# HIVDC.net
KiCad netlist of a schematic drawn in EAGLE
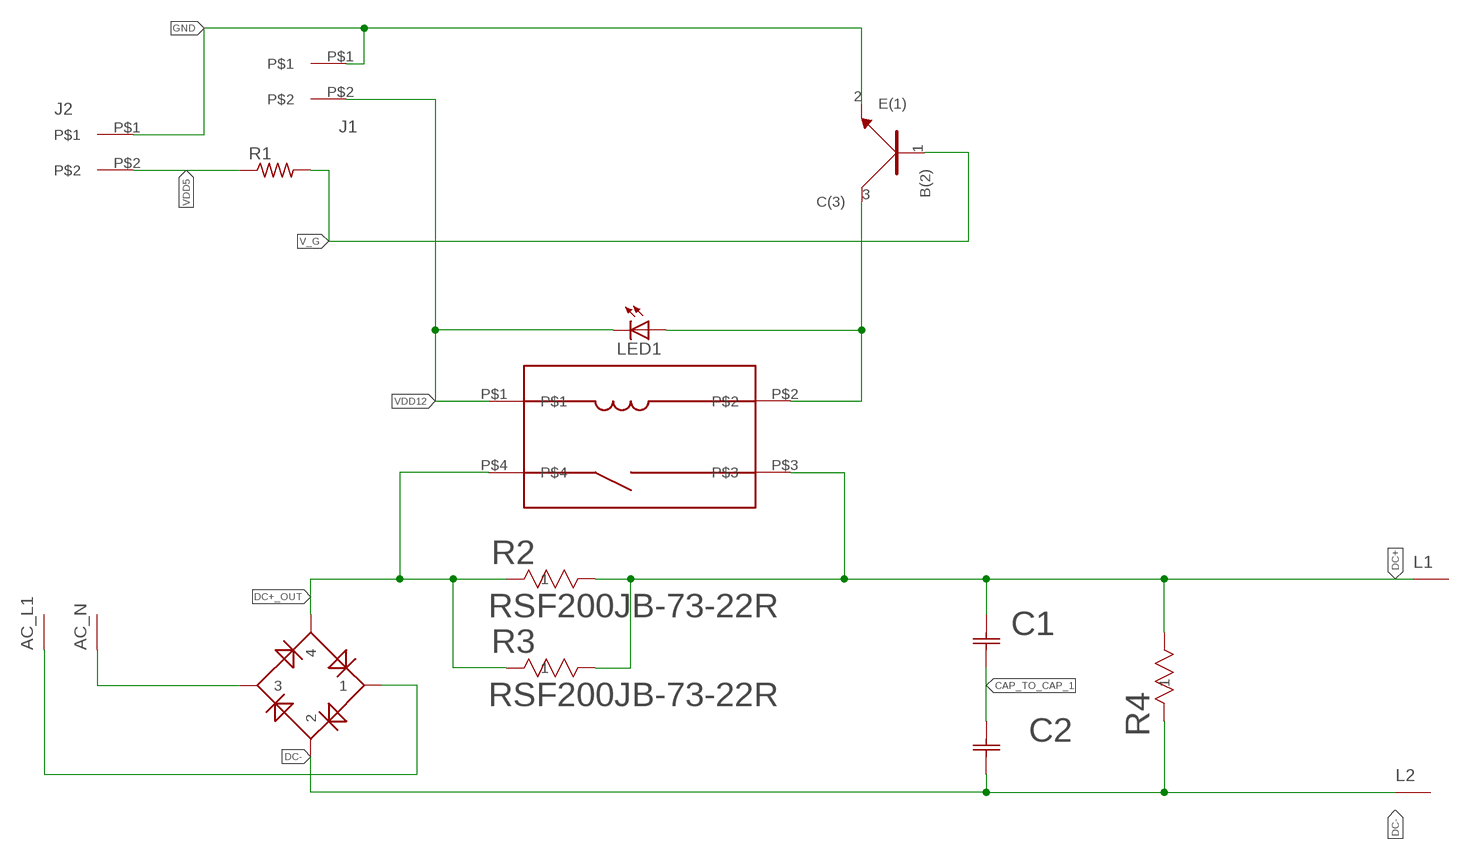
[diagram p0: schematic, sheet 1]

(export (version "E")
  (design (tool "Eeschema 10.0.6"))
  (components
    (comp (ref "AC_L1")
      (value "AC_240V_L_15A")
      (footprint "eagle-import:AC_240V_L1_15A")
      (libsource (lib "eagle-import") (part "AC_240V_L_15A"))
    )
    (comp (ref "AC_N")
      (value "AC_240V_N_15A")
      (footprint "eagle-import:AC_240V_L1_15A")
      (libsource (lib "eagle-import") (part "AC_240V_N_15A"))
    )
    (comp (ref "C1")
      (value "SLP152M250H9P3")
      (footprint "eagle-import:CAP_SLP152M250H9P3_CND")
      (fields (field (name "COPYRIGHT") "Copyright (C) 2018 Accelerated Designs. All rights reserved"))
      (libsource (lib "eagle-import") (part "SLP152M250H9P3"))
    )
    (comp (ref "C2")
      (value "SLP152M250H9P3")
      (footprint "eagle-import:CAP_SLP152M250H9P3_CND")
      (fields (field (name "COPYRIGHT") "Copyright (C) 2018 Accelerated Designs. All rights reserved"))
      (libsource (lib "eagle-import") (part "SLP152M250H9P3"))
    )
    (comp (ref "J1")
      (value "2-pos")
      (footprint "eagle-import:2_3.81MM_PITCH")
      (fields (field (name "PARTNO") "691322310002"))
      (libsource (lib "eagle-import") (part "3.81MM_1_X_2_RT_ANGLE_PLUG_HEADER"))
    )
    (comp (ref "J2")
      (value "2-pos")
      (footprint "eagle-import:2_3.81MM_PITCH")
      (fields (field (name "PARTNO") "691322310002"))
      (libsource (lib "eagle-import") (part "3.81MM_1_X_2_RT_ANGLE_PLUG_HEADER"))
    )
    (comp (ref "L1")
      (value "DC_HI_V")
      (footprint "eagle-import:AC_240V_L1_15A")
      (libsource (lib "eagle-import") (part "DC_HI_V"))
    )
    (comp (ref "L2")
      (value "DC_HI_V")
      (footprint "eagle-import:AC_240V_L1_15A")
      (libsource (lib "eagle-import") (part "DC_HI_V"))
    )
    (comp (ref "LED1")
      (value "Green")
      (footprint "eagle-import:0805")
      (fields (field (name "PARTNO") "LG R971-KN-1"))
      (libsource (lib "eagle-import") (part "LED_0805_GREEN"))
    )
    (comp (ref "R1")
      (value "R_0402")
      (footprint "eagle-import:0402")
      (libsource (lib "eagle-import") (part "R_0402"))
    )
    (comp (ref "R2")
      (value "RSF200JB-73-22R")
      (footprint "eagle-import:YAG_RSF200_YAG")
      (libsource (lib "eagle-import") (part "RSF200JB-73-22R"))
    )
    (comp (ref "R3")
      (value "RSF200JB-73-22R")
      (footprint "eagle-import:YAG_RSF200_YAG")
      (libsource (lib "eagle-import") (part "RSF200JB-73-22R"))
    )
    (comp (ref "R4")
      (value "RS00547K00FE73")
      (footprint "eagle-import:RS005_VIS")
      (libsource (lib "eagle-import") (part "RS00547K00FE73"))
    )
    (comp (ref "RL1")
      (value "J120D1AS12VDCP")
      (footprint "eagle-import:J120D")
      (libsource (lib "eagle-import") (part "J120D1AS12VDCP"))
    )
    (comp (ref "U$1")
      (value "KBPC5010W-G")
      (footprint "eagle-import:KBPC-W_THRU")
      (libsource (lib "eagle-import") (part "KBPC5010W-G"))
    )
    (comp (ref "U1")
      (value "NPN")
      (footprint "eagle-import:SOT323")
      (fields (field (name "PARTNO") "BC846BW_NPN"))
      (libsource (lib "eagle-import") (part "BC846BW"))
    )
  )
  (nets
    (net (code "1") (name "CAP_TO_CAP_1") (class "Default")
      (node (ref "C1") (pin "2") (pinfunction "2_2") (pintype "passive"))
      (node (ref "C2") (pin "1") (pinfunction "1_1") (pintype "passive"))
    )
    (net (code "2") (name "DC+") (class "Default")
      (node (ref "C1") (pin "1") (pinfunction "1_1") (pintype "passive"))
      (node (ref "L1") (pin "P$1") (pinfunction "P$1_P$1") (pintype "passive"))
      (node (ref "R2") (pin "2") (pinfunction "2_2") (pintype "passive"))
      (node (ref "R3") (pin "2") (pinfunction "2_2") (pintype "passive"))
      (node (ref "R4") (pin "2") (pinfunction "2_2") (pintype "passive"))
      (node (ref "RL1") (pin "P$3") (pinfunction "P$3_P$3") (pintype "bidirectional"))
    )
    (net (code "3") (name "DC+_OUT") (class "Default")
      (node (ref "R2") (pin "1") (pinfunction "1_1") (pintype "passive"))
      (node (ref "R3") (pin "1") (pinfunction "1_1") (pintype "passive"))
      (node (ref "RL1") (pin "P$4") (pinfunction "P$4_P$4") (pintype "bidirectional"))
      (node (ref "U$1") (pin "4") (pinfunction "4_4") (pintype "passive"))
    )
    (net (code "4") (name "DC-") (class "Default")
      (node (ref "C2") (pin "2") (pinfunction "2_2") (pintype "passive"))
      (node (ref "L2") (pin "P$1") (pinfunction "P$1_P$1") (pintype "passive"))
      (node (ref "R4") (pin "1") (pinfunction "1_1") (pintype "passive"))
      (node (ref "U$1") (pin "2") (pinfunction "2_2") (pintype "passive"))
    )
    (net (code "5") (name "GND") (class "Default")
      (node (ref "J1") (pin "P$1") (pinfunction "P$1_P$1") (pintype "bidirectional"))
      (node (ref "J2") (pin "P$1") (pinfunction "P$1_P$1") (pintype "bidirectional"))
      (node (ref "U1") (pin "2") (pinfunction "E(1)_2") (pintype "output"))
    )
    (net (code "6") (name "Net-(AC_L1-PadP$1)") (class "Default")
      (node (ref "AC_L1") (pin "P$1") (pinfunction "P$1_P$1") (pintype "passive"))
      (node (ref "U$1") (pin "1") (pinfunction "1_1") (pintype "passive"))
    )
    (net (code "7") (name "Net-(AC_N-PadP$1)") (class "Default")
      (node (ref "AC_N") (pin "P$1") (pinfunction "P$1_P$1") (pintype "passive"))
      (node (ref "U$1") (pin "3") (pinfunction "3_3") (pintype "passive"))
    )
    (net (code "8") (name "Net-(LED1-A)") (class "Default")
      (node (ref "LED1") (pin "1") (pinfunction "A_1") (pintype "passive"))
      (node (ref "RL1") (pin "P$2") (pinfunction "P$2_P$2") (pintype "bidirectional"))
      (node (ref "U1") (pin "3") (pinfunction "C(3)_3") (pintype "input"))
    )
    (net (code "9") (name "VDD5") (class "Default")
      (node (ref "J2") (pin "P$2") (pinfunction "P$2_P$2") (pintype "bidirectional"))
      (node (ref "R1") (pin "P$1") (pinfunction "1_P$1") (pintype "passive"))
    )
    (net (code "10") (name "VDD12") (class "Default")
      (node (ref "J1") (pin "P$2") (pinfunction "P$2_P$2") (pintype "bidirectional"))
      (node (ref "LED1") (pin "2") (pinfunction "C_2") (pintype "passive"))
      (node (ref "RL1") (pin "P$1") (pinfunction "P$1_P$1") (pintype "bidirectional"))
    )
    (net (code "11") (name "V_G") (class "Default")
      (node (ref "R1") (pin "P$2") (pinfunction "2_P$2") (pintype "passive"))
      (node (ref "U1") (pin "1") (pinfunction "B(2)_1") (pintype "input"))
    )
  )
)
